# aecho.net
KiCad netlist of a schematic drawn in EAGLE
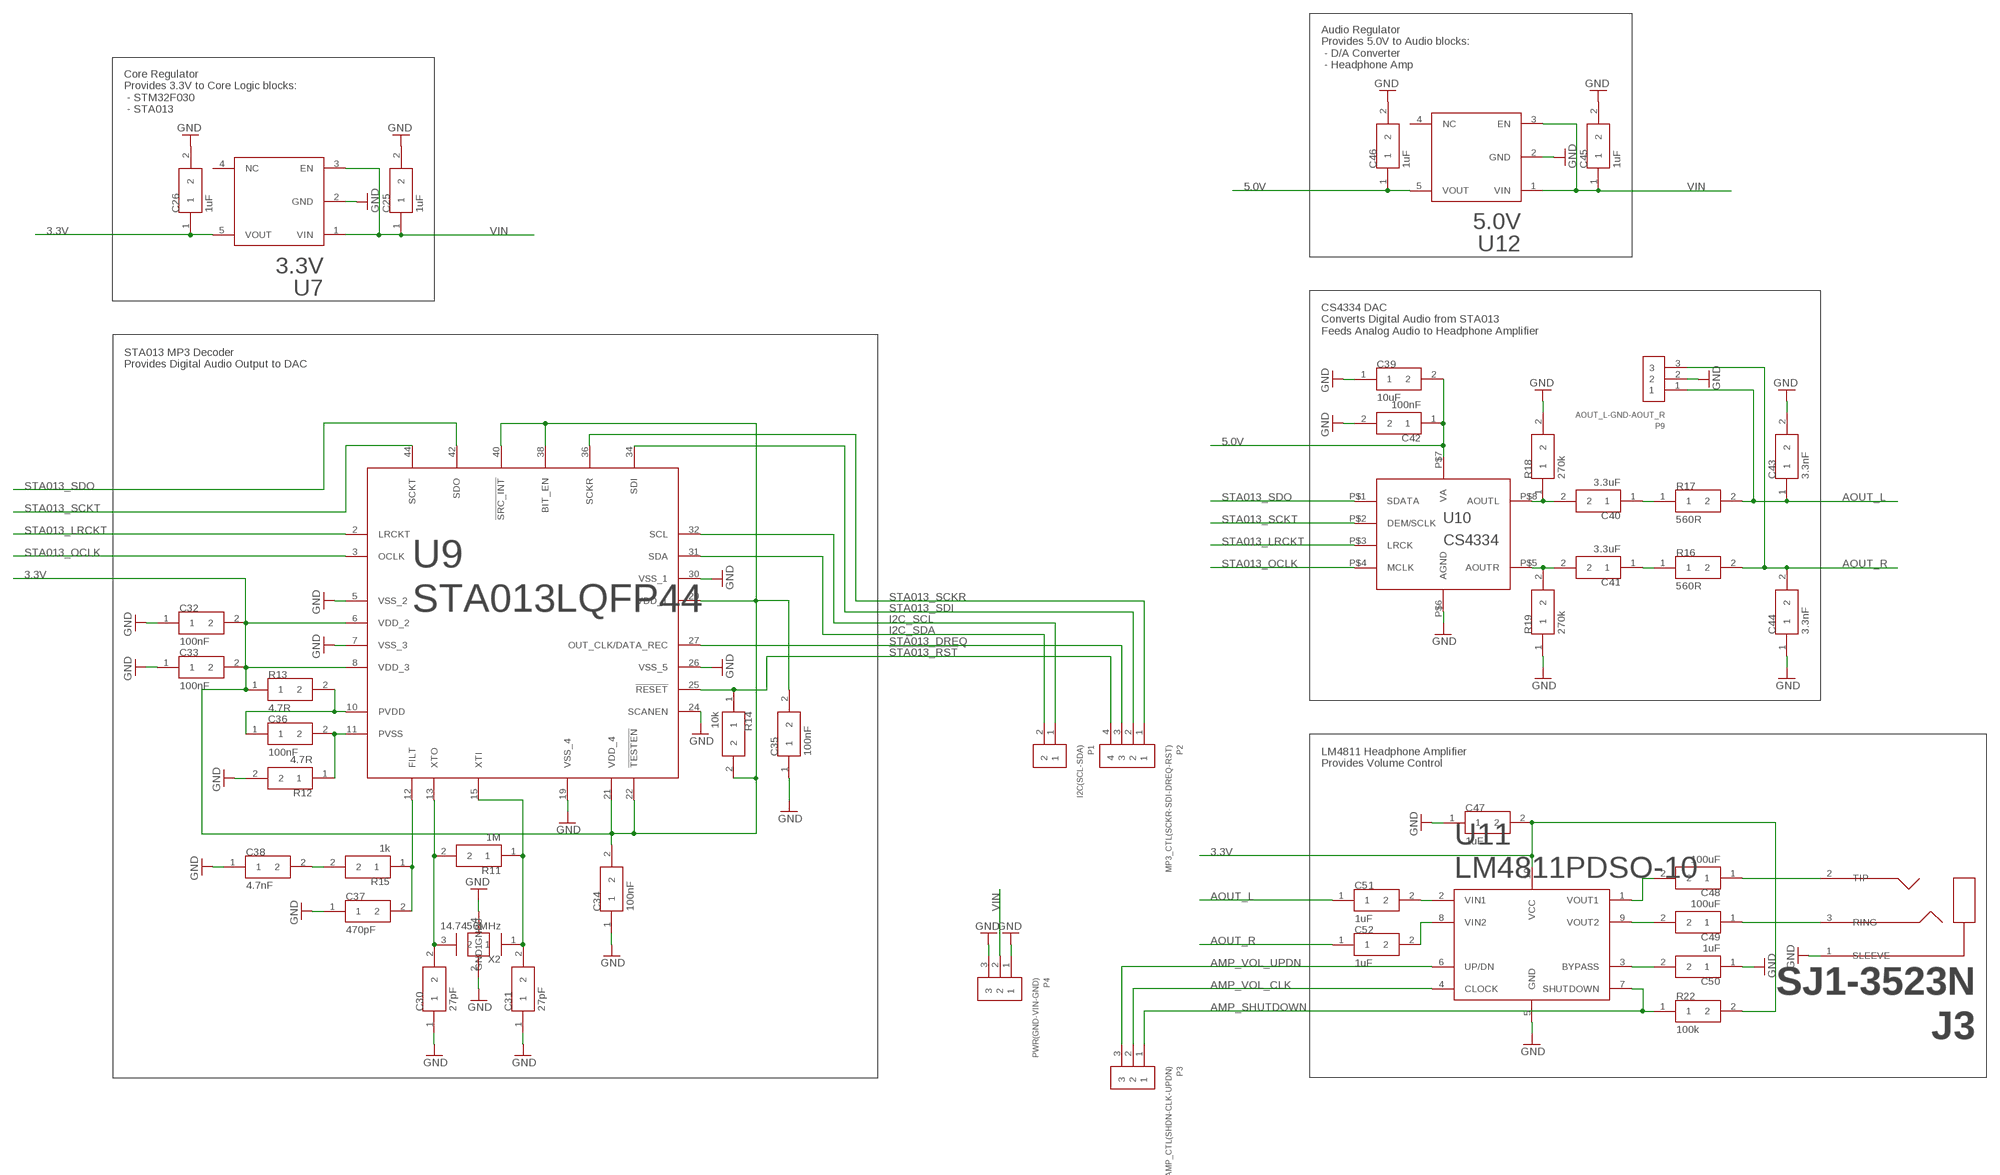
[diagram p0: schematic, sheet 1]

(export (version "E")
  (design (tool "Eeschema 10.0.6"))
  (components
    (comp (ref "C25")
      (value "1uF")
      (footprint "eagle-import:0805")
      (libsource (lib "eagle-import") (part "CAP0805"))
    )
    (comp (ref "C26")
      (value "1uF")
      (footprint "eagle-import:0805")
      (libsource (lib "eagle-import") (part "CAP0805"))
    )
    (comp (ref "C30")
      (value "27pF")
      (footprint "eagle-import:0805")
      (libsource (lib "eagle-import") (part "CAP0805"))
    )
    (comp (ref "C31")
      (value "27pF")
      (footprint "eagle-import:0805")
      (libsource (lib "eagle-import") (part "CAP0805"))
    )
    (comp (ref "C32")
      (value "100nF")
      (footprint "eagle-import:0805")
      (libsource (lib "eagle-import") (part "CAP0805"))
    )
    (comp (ref "C33")
      (value "100nF")
      (footprint "eagle-import:0805")
      (libsource (lib "eagle-import") (part "CAP0805"))
    )
    (comp (ref "C34")
      (value "100nF")
      (footprint "eagle-import:0805")
      (libsource (lib "eagle-import") (part "CAP0805"))
    )
    (comp (ref "C35")
      (value "100nF")
      (footprint "eagle-import:0805")
      (libsource (lib "eagle-import") (part "CAP0805"))
    )
    (comp (ref "C36")
      (value "100nF")
      (footprint "eagle-import:0805")
      (libsource (lib "eagle-import") (part "CAP0805"))
    )
    (comp (ref "C37")
      (value "470pF")
      (footprint "eagle-import:0805")
      (libsource (lib "eagle-import") (part "CAP0805"))
    )
    (comp (ref "C38")
      (value "4.7nF")
      (footprint "eagle-import:0805")
      (libsource (lib "eagle-import") (part "CAP0805"))
    )
    (comp (ref "C39")
      (value "10uF")
      (footprint "eagle-import:0805")
      (libsource (lib "eagle-import") (part "CAP0805"))
    )
    (comp (ref "C40")
      (value "3.3uF")
      (footprint "eagle-import:0805")
      (libsource (lib "eagle-import") (part "CAP0805"))
    )
    (comp (ref "C41")
      (value "3.3uF")
      (footprint "eagle-import:0805")
      (libsource (lib "eagle-import") (part "CAP0805"))
    )
    (comp (ref "C42")
      (value "100nF")
      (footprint "eagle-import:0805")
      (libsource (lib "eagle-import") (part "CAP0805"))
    )
    (comp (ref "C43")
      (value "3.3nF")
      (footprint "eagle-import:0805")
      (libsource (lib "eagle-import") (part "CAP0805"))
    )
    (comp (ref "C44")
      (value "3.3nF")
      (footprint "eagle-import:0805")
      (libsource (lib "eagle-import") (part "CAP0805"))
    )
    (comp (ref "C45")
      (value "1uF")
      (footprint "eagle-import:0805")
      (libsource (lib "eagle-import") (part "CAP0805"))
    )
    (comp (ref "C46")
      (value "1uF")
      (footprint "eagle-import:0805")
      (libsource (lib "eagle-import") (part "CAP0805"))
    )
    (comp (ref "C47")
      (value "1uF")
      (footprint "eagle-import:0805")
      (libsource (lib "eagle-import") (part "CAP0805"))
    )
    (comp (ref "C48")
      (value "100uF")
      (footprint "eagle-import:1210")
      (libsource (lib "eagle-import") (part "CAP1210"))
    )
    (comp (ref "C49")
      (value "100uF")
      (footprint "eagle-import:1210")
      (libsource (lib "eagle-import") (part "CAP1210"))
    )
    (comp (ref "C50")
      (value "1uF")
      (footprint "eagle-import:0805")
      (libsource (lib "eagle-import") (part "CAP0805"))
    )
    (comp (ref "C51")
      (value "1uF")
      (footprint "eagle-import:0805")
      (libsource (lib "eagle-import") (part "CAP0805"))
    )
    (comp (ref "C52")
      (value "1uF")
      (footprint "eagle-import:0805")
      (libsource (lib "eagle-import") (part "CAP0805"))
    )
    (comp (ref "J3")
      (value "SJ1-3523N")
      (footprint "eagle-import:SJ1-352XN")
      (libsource (lib "eagle-import") (part "SJ1-3523N"))
    )
    (comp (ref "P1")
      (value "I2C(SCL-SDA)")
      (footprint "eagle-import:PIN_2")
      (libsource (lib "eagle-import") (part "PIN_2"))
    )
    (comp (ref "P2")
      (value "MP3_CTL(SCKR-SDI-DREQ-RST)")
      (footprint "eagle-import:PIN_4")
      (libsource (lib "eagle-import") (part "PIN_4"))
    )
    (comp (ref "P3")
      (value "AMP_CTL(SHDN-CLK-UPDN)")
      (footprint "eagle-import:PIN_3")
      (libsource (lib "eagle-import") (part "PIN_3"))
    )
    (comp (ref "P4")
      (value "PWR(GND-VIN-GND)")
      (footprint "eagle-import:PIN_3")
      (libsource (lib "eagle-import") (part "PIN_3"))
    )
    (comp (ref "P9")
      (value "AOUT_L-GND-AOUT_R")
      (footprint "eagle-import:PIN_3")
      (libsource (lib "eagle-import") (part "PIN_3"))
    )
    (comp (ref "R11")
      (value "1M")
      (footprint "eagle-import:0805")
      (libsource (lib "eagle-import") (part "RES0805"))
    )
    (comp (ref "R12")
      (value "4.7R")
      (footprint "eagle-import:0805")
      (libsource (lib "eagle-import") (part "RES0805"))
    )
    (comp (ref "R13")
      (value "4.7R")
      (footprint "eagle-import:0805")
      (libsource (lib "eagle-import") (part "RES0805"))
    )
    (comp (ref "R14")
      (value "10k")
      (footprint "eagle-import:0805")
      (libsource (lib "eagle-import") (part "RES0805"))
    )
    (comp (ref "R15")
      (value "1k")
      (footprint "eagle-import:0805")
      (libsource (lib "eagle-import") (part "RES0805"))
    )
    (comp (ref "R16")
      (value "560R")
      (footprint "eagle-import:0805")
      (libsource (lib "eagle-import") (part "RES0805"))
    )
    (comp (ref "R17")
      (value "560R")
      (footprint "eagle-import:0805")
      (libsource (lib "eagle-import") (part "RES0805"))
    )
    (comp (ref "R18")
      (value "270k")
      (footprint "eagle-import:0805")
      (libsource (lib "eagle-import") (part "RES0805"))
    )
    (comp (ref "R19")
      (value "270k")
      (footprint "eagle-import:0805")
      (libsource (lib "eagle-import") (part "RES0805"))
    )
    (comp (ref "R22")
      (value "100k")
      (footprint "eagle-import:0805")
      (libsource (lib "eagle-import") (part "RES0805"))
    )
    (comp (ref "U7")
      (value "3.3V")
      (footprint "eagle-import:SOT23-5")
      (libsource (lib "eagle-import") (part "LP3985SOT23-5"))
    )
    (comp (ref "U9")
      (value "STA013LQFP44")
      (footprint "eagle-import:QFP44")
      (libsource (lib "eagle-import") (part "STA013LQFP44"))
    )
    (comp (ref "U10")
      (value "CS4334")
      (footprint "eagle-import:SO8")
      (libsource (lib "eagle-import") (part "CS4334"))
    )
    (comp (ref "U11")
      (value "LM4811PDSO-10")
      (footprint "eagle-import:PDSO-10")
      (libsource (lib "eagle-import") (part "LM4811PDSO-10"))
    )
    (comp (ref "U12")
      (value "5.0V")
      (footprint "eagle-import:SOT23-5")
      (libsource (lib "eagle-import") (part "LP3985SOT23-5"))
    )
    (comp (ref "X2")
      (value "14.7456MHz")
      (footprint "eagle-import:XTAL_3225")
      (libsource (lib "eagle-import") (part "XTAL_GNDSMD_3225"))
    )
  )
  (nets
    (net (code "1") (name "/3.3V") (class "Default")
      (node (ref "C26") (pin "1") (pinfunction "1_1") (pintype "bidirectional"))
      (node (ref "C32") (pin "2") (pinfunction "2_2") (pintype "bidirectional"))
      (node (ref "C33") (pin "2") (pinfunction "2_2") (pintype "bidirectional"))
      (node (ref "C34") (pin "2") (pinfunction "2_2") (pintype "bidirectional"))
      (node (ref "C35") (pin "2") (pinfunction "2_2") (pintype "bidirectional"))
      (node (ref "C47") (pin "2") (pinfunction "2_2") (pintype "bidirectional"))
      (node (ref "R13") (pin "1") (pinfunction "1_1") (pintype "bidirectional"))
      (node (ref "R14") (pin "2") (pinfunction "2_2") (pintype "bidirectional"))
      (node (ref "R22") (pin "2") (pinfunction "2_2") (pintype "bidirectional"))
      (node (ref "U11") (pin "10") (pinfunction "VCC_10") (pintype "bidirectional"))
      (node (ref "U7") (pin "5") (pinfunction "VOUT_5") (pintype "bidirectional"))
      (node (ref "U9") (pin "21") (pinfunction "VDD_4_21") (pintype "bidirectional"))
      (node (ref "U9") (pin "22") (pinfunction "~{TESTEN}_22") (pintype "bidirectional"))
      (node (ref "U9") (pin "29") (pinfunction "VDD_1_29") (pintype "bidirectional"))
      (node (ref "U9") (pin "38") (pinfunction "BIT_EN_38") (pintype "bidirectional"))
      (node (ref "U9") (pin "40") (pinfunction "~{SRC_INT}_40") (pintype "bidirectional"))
      (node (ref "U9") (pin "6") (pinfunction "VDD_2_6") (pintype "bidirectional"))
      (node (ref "U9") (pin "8") (pinfunction "VDD_3_8") (pintype "bidirectional"))
    )
    (net (code "2") (name "/5.0V") (class "Default")
      (node (ref "C39") (pin "2") (pinfunction "2_2") (pintype "bidirectional"))
      (node (ref "C42") (pin "1") (pinfunction "1_1") (pintype "bidirectional"))
      (node (ref "C46") (pin "1") (pinfunction "1_1") (pintype "bidirectional"))
      (node (ref "U10") (pin "P$7") (pinfunction "VA_P$7") (pintype "bidirectional"))
      (node (ref "U12") (pin "5") (pinfunction "VOUT_5") (pintype "bidirectional"))
    )
    (net (code "3") (name "/AMP_SHUTDOWN") (class "Default")
      (node (ref "P3") (pin "1") (pinfunction "1_1") (pintype "bidirectional"))
      (node (ref "R22") (pin "1") (pinfunction "1_1") (pintype "bidirectional"))
      (node (ref "U11") (pin "7") (pinfunction "SHUTDOWN_7") (pintype "bidirectional"))
    )
    (net (code "4") (name "/AMP_VOL_CLK") (class "Default")
      (node (ref "P3") (pin "2") (pinfunction "2_2") (pintype "bidirectional"))
      (node (ref "U11") (pin "4") (pinfunction "CLOCK_4") (pintype "bidirectional"))
    )
    (net (code "5") (name "/AMP_VOL_UPDN") (class "Default")
      (node (ref "P3") (pin "3") (pinfunction "3_3") (pintype "bidirectional"))
      (node (ref "U11") (pin "6") (pinfunction "UP/DN_6") (pintype "bidirectional"))
    )
    (net (code "6") (name "/AOUT_L") (class "Default")
      (node (ref "C43") (pin "1") (pinfunction "1_1") (pintype "bidirectional"))
      (node (ref "C51") (pin "1") (pinfunction "1_1") (pintype "bidirectional"))
      (node (ref "P9") (pin "1") (pinfunction "1_1") (pintype "bidirectional"))
      (node (ref "R17") (pin "2") (pinfunction "2_2") (pintype "bidirectional"))
    )
    (net (code "7") (name "/AOUT_R") (class "Default")
      (node (ref "C44") (pin "2") (pinfunction "2_2") (pintype "bidirectional"))
      (node (ref "C52") (pin "1") (pinfunction "1_1") (pintype "bidirectional"))
      (node (ref "P9") (pin "3") (pinfunction "3_3") (pintype "bidirectional"))
      (node (ref "R16") (pin "2") (pinfunction "2_2") (pintype "bidirectional"))
    )
    (net (code "8") (name "/I2C_SCL") (class "Default")
      (node (ref "P1") (pin "1") (pinfunction "1_1") (pintype "bidirectional"))
      (node (ref "U9") (pin "32") (pinfunction "SCL_32") (pintype "bidirectional"))
    )
    (net (code "9") (name "/I2C_SDA") (class "Default")
      (node (ref "P1") (pin "2") (pinfunction "2_2") (pintype "bidirectional"))
      (node (ref "U9") (pin "31") (pinfunction "SDA_31") (pintype "bidirectional"))
    )
    (net (code "10") (name "/STA013_DREQ") (class "Default")
      (node (ref "P2") (pin "3") (pinfunction "3_3") (pintype "bidirectional"))
      (node (ref "U9") (pin "27") (pinfunction "OUT_CLK/DATA_REC_27") (pintype "bidirectional"))
    )
    (net (code "11") (name "/STA013_LRCKT") (class "Default")
      (node (ref "U10") (pin "P$3") (pinfunction "LRCK_P$3") (pintype "bidirectional"))
      (node (ref "U9") (pin "2") (pinfunction "LRCKT_2") (pintype "bidirectional"))
    )
    (net (code "12") (name "/STA013_OCLK") (class "Default")
      (node (ref "U10") (pin "P$4") (pinfunction "MCLK_P$4") (pintype "bidirectional"))
      (node (ref "U9") (pin "3") (pinfunction "OCLK_3") (pintype "bidirectional"))
    )
    (net (code "13") (name "/STA013_SCKR") (class "Default")
      (node (ref "P2") (pin "1") (pinfunction "1_1") (pintype "bidirectional"))
      (node (ref "U9") (pin "36") (pinfunction "SCKR_36") (pintype "bidirectional"))
    )
    (net (code "14") (name "/STA013_SCKT") (class "Default")
      (node (ref "U10") (pin "P$2") (pinfunction "DEM/SCLK_P$2") (pintype "bidirectional"))
      (node (ref "U9") (pin "44") (pinfunction "SCKT_44") (pintype "bidirectional"))
    )
    (net (code "15") (name "/STA013_SDI") (class "Default")
      (node (ref "P2") (pin "2") (pinfunction "2_2") (pintype "bidirectional"))
      (node (ref "U9") (pin "34") (pinfunction "SDI_34") (pintype "bidirectional"))
    )
    (net (code "16") (name "/STA013_SDO") (class "Default")
      (node (ref "U10") (pin "P$1") (pinfunction "SDATA_P$1") (pintype "bidirectional"))
      (node (ref "U9") (pin "42") (pinfunction "SDO_42") (pintype "bidirectional"))
    )
    (net (code "17") (name "/VIN") (class "Default")
      (node (ref "C25") (pin "1") (pinfunction "1_1") (pintype "bidirectional"))
      (node (ref "C45") (pin "1") (pinfunction "1_1") (pintype "bidirectional"))
      (node (ref "P4") (pin "2") (pinfunction "2_2") (pintype "bidirectional"))
      (node (ref "U12") (pin "1") (pinfunction "VIN_1") (pintype "bidirectional"))
      (node (ref "U12") (pin "3") (pinfunction "EN_3") (pintype "bidirectional"))
      (node (ref "U7") (pin "1") (pinfunction "VIN_1") (pintype "bidirectional"))
      (node (ref "U7") (pin "3") (pinfunction "EN_3") (pintype "bidirectional"))
    )
    (net (code "18") (name "/~{STA013_RST}") (class "Default")
      (node (ref "P2") (pin "4") (pinfunction "4_4") (pintype "bidirectional"))
      (node (ref "R14") (pin "1") (pinfunction "1_1") (pintype "bidirectional"))
      (node (ref "U9") (pin "25") (pinfunction "~{RESET}_25") (pintype "bidirectional"))
    )
    (net (code "19") (name "GND") (class "Default")
      (node (ref "C25") (pin "2") (pinfunction "2_2") (pintype "bidirectional"))
      (node (ref "C26") (pin "2") (pinfunction "2_2") (pintype "bidirectional"))
      (node (ref "C30") (pin "1") (pinfunction "1_1") (pintype "bidirectional"))
      (node (ref "C31") (pin "1") (pinfunction "1_1") (pintype "bidirectional"))
      (node (ref "C32") (pin "1") (pinfunction "1_1") (pintype "bidirectional"))
      (node (ref "C33") (pin "1") (pinfunction "1_1") (pintype "bidirectional"))
      (node (ref "C34") (pin "1") (pinfunction "1_1") (pintype "bidirectional"))
      (node (ref "C35") (pin "1") (pinfunction "1_1") (pintype "bidirectional"))
      (node (ref "C37") (pin "1") (pinfunction "1_1") (pintype "bidirectional"))
      (node (ref "C38") (pin "1") (pinfunction "1_1") (pintype "bidirectional"))
      (node (ref "C39") (pin "1") (pinfunction "1_1") (pintype "bidirectional"))
      (node (ref "C42") (pin "2") (pinfunction "2_2") (pintype "bidirectional"))
      (node (ref "C43") (pin "2") (pinfunction "2_2") (pintype "bidirectional"))
      (node (ref "C44") (pin "1") (pinfunction "1_1") (pintype "bidirectional"))
      (node (ref "C45") (pin "2") (pinfunction "2_2") (pintype "bidirectional"))
      (node (ref "C46") (pin "2") (pinfunction "2_2") (pintype "bidirectional"))
      (node (ref "C47") (pin "1") (pinfunction "1_1") (pintype "bidirectional"))
      (node (ref "C50") (pin "1") (pinfunction "1_1") (pintype "bidirectional"))
      (node (ref "J3") (pin "1") (pinfunction "SLEEVE_1") (pintype "bidirectional"))
      (node (ref "P4") (pin "1") (pinfunction "1_1") (pintype "bidirectional"))
      (node (ref "P4") (pin "3") (pinfunction "3_3") (pintype "bidirectional"))
      (node (ref "P9") (pin "2") (pinfunction "2_2") (pintype "bidirectional"))
      (node (ref "R12") (pin "2") (pinfunction "2_2") (pintype "bidirectional"))
      (node (ref "R18") (pin "2") (pinfunction "2_2") (pintype "bidirectional"))
      (node (ref "R19") (pin "1") (pinfunction "1_1") (pintype "bidirectional"))
      (node (ref "U10") (pin "P$6") (pinfunction "AGND_P$6") (pintype "bidirectional"))
      (node (ref "U11") (pin "5") (pinfunction "GND_5") (pintype "bidirectional"))
      (node (ref "U12") (pin "2") (pinfunction "GND_2") (pintype "bidirectional"))
      (node (ref "U7") (pin "2") (pinfunction "GND_2") (pintype "bidirectional"))
      (node (ref "U9") (pin "19") (pinfunction "VSS_4_19") (pintype "bidirectional"))
      (node (ref "U9") (pin "24") (pinfunction "SCANEN_24") (pintype "bidirectional"))
      (node (ref "U9") (pin "26") (pinfunction "VSS_5_26") (pintype "bidirectional"))
      (node (ref "U9") (pin "30") (pinfunction "VSS_1_30") (pintype "bidirectional"))
      (node (ref "U9") (pin "5") (pinfunction "VSS_2_5") (pintype "bidirectional"))
      (node (ref "U9") (pin "7") (pinfunction "VSS_3_7") (pintype "bidirectional"))
      (node (ref "X2") (pin "2") (pinfunction "GND0_2") (pintype "bidirectional"))
      (node (ref "X2") (pin "4") (pinfunction "GND1_4") (pintype "bidirectional"))
    )
    (net (code "20") (name "Net-(C38-Pad2)") (class "Default")
      (node (ref "C38") (pin "2") (pinfunction "2_2") (pintype "bidirectional"))
      (node (ref "R15") (pin "2") (pinfunction "2_2") (pintype "bidirectional"))
    )
    (net (code "21") (name "Net-(C40-Pad1)") (class "Default")
      (node (ref "C40") (pin "1") (pinfunction "1_1") (pintype "bidirectional"))
      (node (ref "R17") (pin "1") (pinfunction "1_1") (pintype "bidirectional"))
    )
    (net (code "22") (name "Net-(C41-Pad1)") (class "Default")
      (node (ref "C41") (pin "1") (pinfunction "1_1") (pintype "bidirectional"))
      (node (ref "R16") (pin "1") (pinfunction "1_1") (pintype "bidirectional"))
    )
    (net (code "23") (name "Net-(J3-RING)") (class "Default")
      (node (ref "C49") (pin "1") (pinfunction "1_1") (pintype "bidirectional"))
      (node (ref "J3") (pin "3") (pinfunction "RING_3") (pintype "bidirectional"))
    )
    (net (code "24") (name "Net-(J3-TIP)") (class "Default")
      (node (ref "C48") (pin "1") (pinfunction "1_1") (pintype "bidirectional"))
      (node (ref "J3") (pin "2") (pinfunction "TIP_2") (pintype "bidirectional"))
    )
    (net (code "25") (name "Net-(U9-FILT)") (class "Default")
      (node (ref "C37") (pin "2") (pinfunction "2_2") (pintype "bidirectional"))
      (node (ref "R15") (pin "1") (pinfunction "1_1") (pintype "bidirectional"))
      (node (ref "U9") (pin "12") (pinfunction "FILT_12") (pintype "bidirectional"))
    )
    (net (code "26") (name "Net-(U9-PVDD)") (class "Default")
      (node (ref "C36") (pin "1") (pinfunction "1_1") (pintype "bidirectional"))
      (node (ref "R13") (pin "2") (pinfunction "2_2") (pintype "bidirectional"))
      (node (ref "U9") (pin "10") (pinfunction "PVDD_10") (pintype "bidirectional"))
    )
    (net (code "27") (name "Net-(U9-PVSS)") (class "Default")
      (node (ref "C36") (pin "2") (pinfunction "2_2") (pintype "bidirectional"))
      (node (ref "R12") (pin "1") (pinfunction "1_1") (pintype "bidirectional"))
      (node (ref "U9") (pin "11") (pinfunction "PVSS_11") (pintype "bidirectional"))
    )
    (net (code "28") (name "Net-(U9-XTI)") (class "Default")
      (node (ref "C31") (pin "2") (pinfunction "2_2") (pintype "bidirectional"))
      (node (ref "R11") (pin "1") (pinfunction "1_1") (pintype "bidirectional"))
      (node (ref "U9") (pin "15") (pinfunction "XTI_15") (pintype "bidirectional"))
      (node (ref "X2") (pin "1") (pinfunction "1_1") (pintype "bidirectional"))
    )
    (net (code "29") (name "Net-(U9-XTO)") (class "Default")
      (node (ref "C30") (pin "2") (pinfunction "2_2") (pintype "bidirectional"))
      (node (ref "R11") (pin "2") (pinfunction "2_2") (pintype "bidirectional"))
      (node (ref "U9") (pin "13") (pinfunction "XTO_13") (pintype "bidirectional"))
      (node (ref "X2") (pin "3") (pinfunction "2_3") (pintype "bidirectional"))
    )
    (net (code "30") (name "Net-(U10-AOUTL)") (class "Default")
      (node (ref "C40") (pin "2") (pinfunction "2_2") (pintype "bidirectional"))
      (node (ref "R18") (pin "1") (pinfunction "1_1") (pintype "bidirectional"))
      (node (ref "U10") (pin "P$8") (pinfunction "AOUTL_P$8") (pintype "bidirectional"))
    )
    (net (code "31") (name "Net-(U10-AOUTR)") (class "Default")
      (node (ref "C41") (pin "2") (pinfunction "2_2") (pintype "bidirectional"))
      (node (ref "R19") (pin "2") (pinfunction "2_2") (pintype "bidirectional"))
      (node (ref "U10") (pin "P$5") (pinfunction "AOUTR_P$5") (pintype "bidirectional"))
    )
    (net (code "32") (name "Net-(U11-BYPASS)") (class "Default")
      (node (ref "C50") (pin "2") (pinfunction "2_2") (pintype "bidirectional"))
      (node (ref "U11") (pin "3") (pinfunction "BYPASS_3") (pintype "bidirectional"))
    )
    (net (code "33") (name "Net-(U11-VIN1)") (class "Default")
      (node (ref "C51") (pin "2") (pinfunction "2_2") (pintype "bidirectional"))
      (node (ref "U11") (pin "2") (pinfunction "VIN1_2") (pintype "bidirectional"))
    )
    (net (code "34") (name "Net-(U11-VIN2)") (class "Default")
      (node (ref "C52") (pin "2") (pinfunction "2_2") (pintype "bidirectional"))
      (node (ref "U11") (pin "8") (pinfunction "VIN2_8") (pintype "bidirectional"))
    )
    (net (code "35") (name "Net-(U11-VOUT1)") (class "Default")
      (node (ref "C48") (pin "2") (pinfunction "2_2") (pintype "bidirectional"))
      (node (ref "U11") (pin "1") (pinfunction "VOUT1_1") (pintype "bidirectional"))
    )
    (net (code "36") (name "Net-(U11-VOUT2)") (class "Default")
      (node (ref "C49") (pin "2") (pinfunction "2_2") (pintype "bidirectional"))
      (node (ref "U11") (pin "9") (pinfunction "VOUT2_9") (pintype "bidirectional"))
    )
    (net (code "37") (name "unconnected-(U7-NC-Pad4)") (class "Default")
      (node (ref "U7") (pin "4") (pinfunction "NC_4") (pintype "bidirectional"))
    )
    (net (code "38") (name "unconnected-(U12-NC-Pad4)") (class "Default")
      (node (ref "U12") (pin "4") (pinfunction "NC_4") (pintype "bidirectional"))
    )
  )
)
